# ext_board.net
KiCad netlist of a schematic drawn in EAGLE
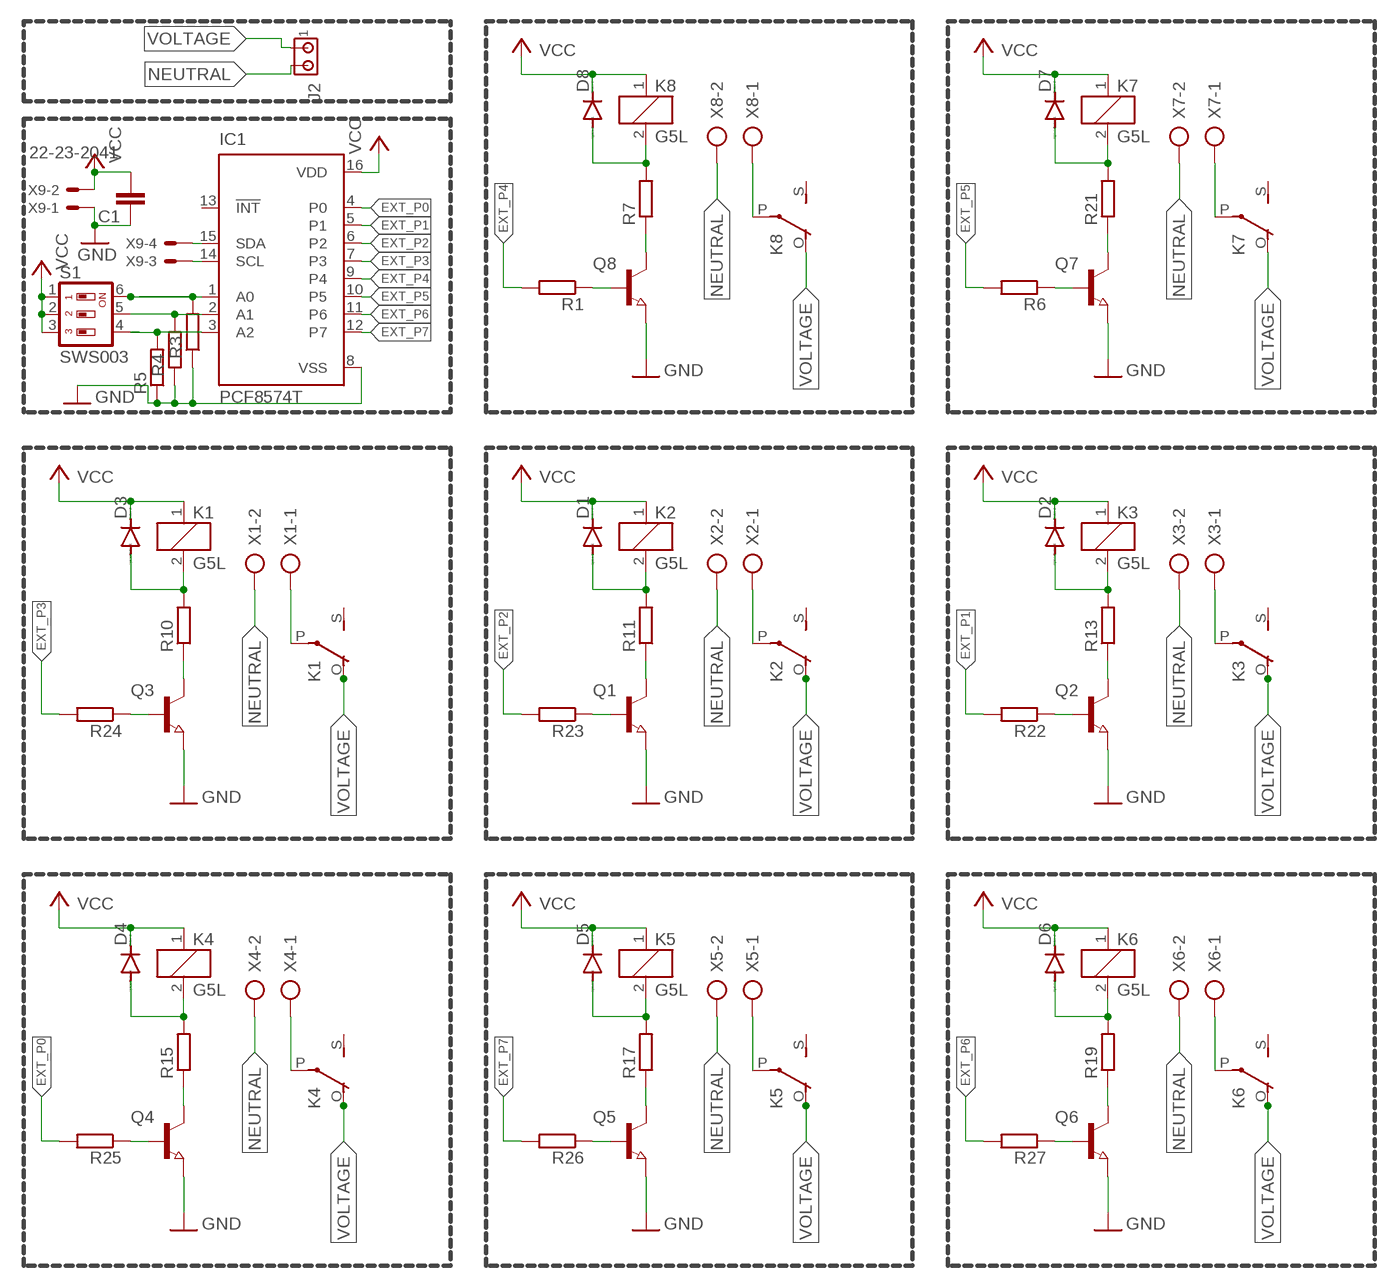
[diagram p0: schematic, sheet 1]

(export (version "E")
  (design (tool "Eeschema 10.0.6"))
  (components
    (comp (ref "C1")
      (value "C-EUC2012")
      (footprint "eagle-import:C2012")
      (libsource (lib "eagle-import") (part "C-EUC2012"))
    )
    (comp (ref "D1")
      (value "DIODE-DO-214AC")
      (footprint "eagle-import:DO-214AC")
      (libsource (lib "eagle-import") (part "DIODE-DO-214AC"))
    )
    (comp (ref "D2")
      (value "DIODE-DO-214AC")
      (footprint "eagle-import:DO-214AC")
      (libsource (lib "eagle-import") (part "DIODE-DO-214AC"))
    )
    (comp (ref "D3")
      (value "DIODE-DO-214AC")
      (footprint "eagle-import:DO-214AC")
      (libsource (lib "eagle-import") (part "DIODE-DO-214AC"))
    )
    (comp (ref "D4")
      (value "DIODE-DO-214AC")
      (footprint "eagle-import:DO-214AC")
      (libsource (lib "eagle-import") (part "DIODE-DO-214AC"))
    )
    (comp (ref "D5")
      (value "DIODE-DO-214AC")
      (footprint "eagle-import:DO-214AC")
      (libsource (lib "eagle-import") (part "DIODE-DO-214AC"))
    )
    (comp (ref "D6")
      (value "DIODE-DO-214AC")
      (footprint "eagle-import:DO-214AC")
      (libsource (lib "eagle-import") (part "DIODE-DO-214AC"))
    )
    (comp (ref "D7")
      (value "DIODE-DO-214AC")
      (footprint "eagle-import:DO-214AC")
      (libsource (lib "eagle-import") (part "DIODE-DO-214AC"))
    )
    (comp (ref "D8")
      (value "DIODE-DO-214AC")
      (footprint "eagle-import:DO-214AC")
      (libsource (lib "eagle-import") (part "DIODE-DO-214AC"))
    )
    (comp (ref "IC1")
      (value "PCF8574T")
      (footprint "eagle-import:SO16W")
      (fields (field (name "MPN") "PCF8574T/3,512"))
      (libsource (lib "eagle-import") (part "PCF8574T"))
    )
    (comp (ref "J2")
      (value "MTA02-156")
      (footprint "eagle-import:1X2MTA")
      (libsource (lib "eagle-import") (part "MTA02-156"))
    )
    (comp (ref "K1")
      (value "G5L")
      (footprint "eagle-import:G5LE")
      (libsource (lib "eagle-import") (part "G5L"))
    )
    (comp (ref "K2")
      (value "G5L")
      (footprint "eagle-import:G5LE")
      (libsource (lib "eagle-import") (part "G5L"))
    )
    (comp (ref "K3")
      (value "G5L")
      (footprint "eagle-import:G5LE")
      (libsource (lib "eagle-import") (part "G5L"))
    )
    (comp (ref "K4")
      (value "G5L")
      (footprint "eagle-import:G5LE")
      (libsource (lib "eagle-import") (part "G5L"))
    )
    (comp (ref "K5")
      (value "G5L")
      (footprint "eagle-import:G5LE")
      (libsource (lib "eagle-import") (part "G5L"))
    )
    (comp (ref "K6")
      (value "G5L")
      (footprint "eagle-import:G5LE")
      (libsource (lib "eagle-import") (part "G5L"))
    )
    (comp (ref "K7")
      (value "G5L")
      (footprint "eagle-import:G5LE")
      (libsource (lib "eagle-import") (part "G5L"))
    )
    (comp (ref "K8")
      (value "G5L")
      (footprint "eagle-import:G5LE")
      (libsource (lib "eagle-import") (part "G5L"))
    )
    (comp (ref "Q1")
      (value "NPN-TRANSISTOR_SOT23")
      (footprint "eagle-import:SOT23")
      (libsource (lib "eagle-import") (part "NPN-TRANSISTOR_SOT23"))
    )
    (comp (ref "Q2")
      (value "NPN-TRANSISTOR_SOT23")
      (footprint "eagle-import:SOT23")
      (libsource (lib "eagle-import") (part "NPN-TRANSISTOR_SOT23"))
    )
    (comp (ref "Q3")
      (value "NPN-TRANSISTOR_SOT23")
      (footprint "eagle-import:SOT23")
      (libsource (lib "eagle-import") (part "NPN-TRANSISTOR_SOT23"))
    )
    (comp (ref "Q4")
      (value "NPN-TRANSISTOR_SOT23")
      (footprint "eagle-import:SOT23")
      (libsource (lib "eagle-import") (part "NPN-TRANSISTOR_SOT23"))
    )
    (comp (ref "Q5")
      (value "NPN-TRANSISTOR_SOT23")
      (footprint "eagle-import:SOT23")
      (libsource (lib "eagle-import") (part "NPN-TRANSISTOR_SOT23"))
    )
    (comp (ref "Q6")
      (value "NPN-TRANSISTOR_SOT23")
      (footprint "eagle-import:SOT23")
      (libsource (lib "eagle-import") (part "NPN-TRANSISTOR_SOT23"))
    )
    (comp (ref "Q7")
      (value "NPN-TRANSISTOR_SOT23")
      (footprint "eagle-import:SOT23")
      (libsource (lib "eagle-import") (part "NPN-TRANSISTOR_SOT23"))
    )
    (comp (ref "Q8")
      (value "NPN-TRANSISTOR_SOT23")
      (footprint "eagle-import:SOT23")
      (libsource (lib "eagle-import") (part "NPN-TRANSISTOR_SOT23"))
    )
    (comp (ref "R1")
      (value "R-EU_R2010")
      (footprint "eagle-import:R2010")
      (libsource (lib "eagle-import") (part "R-EU_R2010"))
    )
    (comp (ref "R3")
      (value "R-EU_M2012")
      (footprint "eagle-import:M2012")
      (libsource (lib "eagle-import") (part "R-EU_M2012"))
    )
    (comp (ref "R4")
      (value "R-EU_M2012")
      (footprint "eagle-import:M2012")
      (libsource (lib "eagle-import") (part "R-EU_M2012"))
    )
    (comp (ref "R5")
      (value "R-EU_M2012")
      (footprint "eagle-import:M2012")
      (libsource (lib "eagle-import") (part "R-EU_M2012"))
    )
    (comp (ref "R6")
      (value "R-EU_R2010")
      (footprint "eagle-import:R2010")
      (libsource (lib "eagle-import") (part "R-EU_R2010"))
    )
    (comp (ref "R7")
      (value "R-EU_M2012")
      (footprint "eagle-import:M2012")
      (libsource (lib "eagle-import") (part "R-EU_M2012"))
    )
    (comp (ref "R10")
      (value "R-EU_M2012")
      (footprint "eagle-import:M2012")
      (libsource (lib "eagle-import") (part "R-EU_M2012"))
    )
    (comp (ref "R11")
      (value "R-EU_M2012")
      (footprint "eagle-import:M2012")
      (libsource (lib "eagle-import") (part "R-EU_M2012"))
    )
    (comp (ref "R13")
      (value "R-EU_M2012")
      (footprint "eagle-import:M2012")
      (libsource (lib "eagle-import") (part "R-EU_M2012"))
    )
    (comp (ref "R15")
      (value "R-EU_M2012")
      (footprint "eagle-import:M2012")
      (libsource (lib "eagle-import") (part "R-EU_M2012"))
    )
    (comp (ref "R17")
      (value "R-EU_M2012")
      (footprint "eagle-import:M2012")
      (libsource (lib "eagle-import") (part "R-EU_M2012"))
    )
    (comp (ref "R19")
      (value "R-EU_M2012")
      (footprint "eagle-import:M2012")
      (libsource (lib "eagle-import") (part "R-EU_M2012"))
    )
    (comp (ref "R21")
      (value "R-EU_M2012")
      (footprint "eagle-import:M2012")
      (libsource (lib "eagle-import") (part "R-EU_M2012"))
    )
    (comp (ref "R22")
      (value "R-EU_R2010")
      (footprint "eagle-import:R2010")
      (libsource (lib "eagle-import") (part "R-EU_R2010"))
    )
    (comp (ref "R23")
      (value "R-EU_R2010")
      (footprint "eagle-import:R2010")
      (libsource (lib "eagle-import") (part "R-EU_R2010"))
    )
    (comp (ref "R24")
      (value "R-EU_R2010")
      (footprint "eagle-import:R2010")
      (libsource (lib "eagle-import") (part "R-EU_R2010"))
    )
    (comp (ref "R25")
      (value "R-EU_R2010")
      (footprint "eagle-import:R2010")
      (libsource (lib "eagle-import") (part "R-EU_R2010"))
    )
    (comp (ref "R26")
      (value "R-EU_R2010")
      (footprint "eagle-import:R2010")
      (libsource (lib "eagle-import") (part "R-EU_R2010"))
    )
    (comp (ref "R27")
      (value "R-EU_R2010")
      (footprint "eagle-import:R2010")
      (libsource (lib "eagle-import") (part "R-EU_R2010"))
    )
    (comp (ref "S1")
      (value "SWS003")
      (footprint "eagle-import:SMS-003")
      (libsource (lib "eagle-import") (part "SWS003"))
    )
    (comp (ref "X1")
      (value "AK300/2")
      (footprint "eagle-import:AK300_2")
      (libsource (lib "eagle-import") (part "AK300/2"))
    )
    (comp (ref "X2")
      (value "AK300/2")
      (footprint "eagle-import:AK300_2")
      (libsource (lib "eagle-import") (part "AK300/2"))
    )
    (comp (ref "X3")
      (value "AK300/2")
      (footprint "eagle-import:AK300_2")
      (libsource (lib "eagle-import") (part "AK300/2"))
    )
    (comp (ref "X4")
      (value "AK300/2")
      (footprint "eagle-import:AK300_2")
      (libsource (lib "eagle-import") (part "AK300/2"))
    )
    (comp (ref "X5")
      (value "AK300/2")
      (footprint "eagle-import:AK300_2")
      (libsource (lib "eagle-import") (part "AK300/2"))
    )
    (comp (ref "X6")
      (value "AK300/2")
      (footprint "eagle-import:AK300_2")
      (libsource (lib "eagle-import") (part "AK300/2"))
    )
    (comp (ref "X7")
      (value "AK300/2")
      (footprint "eagle-import:AK300_2")
      (libsource (lib "eagle-import") (part "AK300/2"))
    )
    (comp (ref "X8")
      (value "AK300/2")
      (footprint "eagle-import:AK300_2")
      (libsource (lib "eagle-import") (part "AK300/2"))
    )
    (comp (ref "X9")
      (value "22-23-2041")
      (footprint "eagle-import:22-23-2041")
      (fields (field (name "MF") "MOLEX"))
      (libsource (lib "eagle-import") (part "22-23-2041"))
    )
  )
  (nets
    (net (code "1") (name "EXT_P0") (class "Default")
      (node (ref "IC1") (pin "4") (pinfunction "P0_4") (pintype "bidirectional"))
      (node (ref "R25") (pin "2") (pinfunction "2_2") (pintype "passive"))
    )
    (net (code "2") (name "EXT_P1") (class "Default")
      (node (ref "IC1") (pin "5") (pinfunction "P1_5") (pintype "bidirectional"))
      (node (ref "R22") (pin "2") (pinfunction "2_2") (pintype "passive"))
    )
    (net (code "3") (name "EXT_P2") (class "Default")
      (node (ref "IC1") (pin "6") (pinfunction "P2_6") (pintype "bidirectional"))
      (node (ref "R23") (pin "2") (pinfunction "2_2") (pintype "passive"))
    )
    (net (code "4") (name "EXT_P3") (class "Default")
      (node (ref "IC1") (pin "7") (pinfunction "P3_7") (pintype "bidirectional"))
      (node (ref "R24") (pin "2") (pinfunction "2_2") (pintype "passive"))
    )
    (net (code "5") (name "EXT_P4") (class "Default")
      (node (ref "IC1") (pin "9") (pinfunction "P4_9") (pintype "bidirectional"))
      (node (ref "R1") (pin "2") (pinfunction "2_2") (pintype "passive"))
    )
    (net (code "6") (name "EXT_P5") (class "Default")
      (node (ref "IC1") (pin "10") (pinfunction "P5_10") (pintype "bidirectional"))
      (node (ref "R6") (pin "2") (pinfunction "2_2") (pintype "passive"))
    )
    (net (code "7") (name "EXT_P6") (class "Default")
      (node (ref "IC1") (pin "11") (pinfunction "P6_11") (pintype "bidirectional"))
      (node (ref "R27") (pin "2") (pinfunction "2_2") (pintype "passive"))
    )
    (net (code "8") (name "EXT_P7") (class "Default")
      (node (ref "IC1") (pin "12") (pinfunction "P7_12") (pintype "bidirectional"))
      (node (ref "R26") (pin "2") (pinfunction "2_2") (pintype "passive"))
    )
    (net (code "9") (name "GND") (class "Default")
      (node (ref "C1") (pin "1") (pinfunction "1_1") (pintype "passive"))
      (node (ref "IC1") (pin "8") (pinfunction "VSS_8") (pintype "power_in"))
      (node (ref "Q1") (pin "2") (pinfunction "E_2") (pintype "passive"))
      (node (ref "Q2") (pin "2") (pinfunction "E_2") (pintype "passive"))
      (node (ref "Q3") (pin "2") (pinfunction "E_2") (pintype "passive"))
      (node (ref "Q4") (pin "2") (pinfunction "E_2") (pintype "passive"))
      (node (ref "Q5") (pin "2") (pinfunction "E_2") (pintype "passive"))
      (node (ref "Q6") (pin "2") (pinfunction "E_2") (pintype "passive"))
      (node (ref "Q7") (pin "2") (pinfunction "E_2") (pintype "passive"))
      (node (ref "Q8") (pin "2") (pinfunction "E_2") (pintype "passive"))
      (node (ref "R3") (pin "1") (pinfunction "1_1") (pintype "passive"))
      (node (ref "R4") (pin "1") (pinfunction "1_1") (pintype "passive"))
      (node (ref "R5") (pin "1") (pinfunction "1_1") (pintype "passive"))
      (node (ref "X9") (pin "1") (pinfunction "S_1") (pintype "passive"))
    )
    (net (code "10") (name "NEUTRAL") (class "Default")
      (node (ref "J2") (pin "2") (pinfunction "2_2") (pintype "passive"))
      (node (ref "X1") (pin "2") (pinfunction "KL_2") (pintype "passive"))
      (node (ref "X2") (pin "2") (pinfunction "KL_2") (pintype "passive"))
      (node (ref "X3") (pin "2") (pinfunction "KL_2") (pintype "passive"))
      (node (ref "X4") (pin "2") (pinfunction "KL_2") (pintype "passive"))
      (node (ref "X5") (pin "2") (pinfunction "KL_2") (pintype "passive"))
      (node (ref "X6") (pin "2") (pinfunction "KL_2") (pintype "passive"))
      (node (ref "X7") (pin "2") (pinfunction "KL_2") (pintype "passive"))
      (node (ref "X8") (pin "2") (pinfunction "KL_2") (pintype "passive"))
    )
    (net (code "11") (name "Net-(D1-PadA)") (class "Default")
      (node (ref "D1") (pin "A") (pinfunction "A_A") (pintype "passive"))
      (node (ref "K2") (pin "2") (pinfunction "2_2") (pintype "passive"))
      (node (ref "R11") (pin "2") (pinfunction "2_2") (pintype "passive"))
    )
    (net (code "12") (name "Net-(D2-PadA)") (class "Default")
      (node (ref "D2") (pin "A") (pinfunction "A_A") (pintype "passive"))
      (node (ref "K3") (pin "2") (pinfunction "2_2") (pintype "passive"))
      (node (ref "R13") (pin "2") (pinfunction "2_2") (pintype "passive"))
    )
    (net (code "13") (name "Net-(D3-PadA)") (class "Default")
      (node (ref "D3") (pin "A") (pinfunction "A_A") (pintype "passive"))
      (node (ref "K1") (pin "2") (pinfunction "2_2") (pintype "passive"))
      (node (ref "R10") (pin "2") (pinfunction "2_2") (pintype "passive"))
    )
    (net (code "14") (name "Net-(D4-PadA)") (class "Default")
      (node (ref "D4") (pin "A") (pinfunction "A_A") (pintype "passive"))
      (node (ref "K4") (pin "2") (pinfunction "2_2") (pintype "passive"))
      (node (ref "R15") (pin "2") (pinfunction "2_2") (pintype "passive"))
    )
    (net (code "15") (name "Net-(D5-PadA)") (class "Default")
      (node (ref "D5") (pin "A") (pinfunction "A_A") (pintype "passive"))
      (node (ref "K5") (pin "2") (pinfunction "2_2") (pintype "passive"))
      (node (ref "R17") (pin "2") (pinfunction "2_2") (pintype "passive"))
    )
    (net (code "16") (name "Net-(D6-PadA)") (class "Default")
      (node (ref "D6") (pin "A") (pinfunction "A_A") (pintype "passive"))
      (node (ref "K6") (pin "2") (pinfunction "2_2") (pintype "passive"))
      (node (ref "R19") (pin "2") (pinfunction "2_2") (pintype "passive"))
    )
    (net (code "17") (name "Net-(D7-PadA)") (class "Default")
      (node (ref "D7") (pin "A") (pinfunction "A_A") (pintype "passive"))
      (node (ref "K7") (pin "2") (pinfunction "2_2") (pintype "passive"))
      (node (ref "R21") (pin "2") (pinfunction "2_2") (pintype "passive"))
    )
    (net (code "18") (name "Net-(D8-PadA)") (class "Default")
      (node (ref "D8") (pin "A") (pinfunction "A_A") (pintype "passive"))
      (node (ref "K8") (pin "2") (pinfunction "2_2") (pintype "passive"))
      (node (ref "R7") (pin "2") (pinfunction "2_2") (pintype "passive"))
    )
    (net (code "19") (name "Net-(IC1-A0)") (class "Default")
      (node (ref "IC1") (pin "1") (pinfunction "A0_1") (pintype "input"))
      (node (ref "R3") (pin "2") (pinfunction "2_2") (pintype "passive"))
      (node (ref "S1") (pin "6") (pinfunction "6_6") (pintype "passive"))
    )
    (net (code "20") (name "Net-(IC1-A1)") (class "Default")
      (node (ref "IC1") (pin "2") (pinfunction "A1_2") (pintype "input"))
      (node (ref "R4") (pin "2") (pinfunction "2_2") (pintype "passive"))
      (node (ref "S1") (pin "5") (pinfunction "5_5") (pintype "passive"))
    )
    (net (code "21") (name "Net-(IC1-A2)") (class "Default")
      (node (ref "IC1") (pin "3") (pinfunction "A2_3") (pintype "input"))
      (node (ref "R5") (pin "2") (pinfunction "2_2") (pintype "passive"))
      (node (ref "S1") (pin "4") (pinfunction "4_4") (pintype "passive"))
    )
    (net (code "22") (name "Net-(IC1-SCL)") (class "Default")
      (node (ref "IC1") (pin "14") (pinfunction "SCL_14") (pintype "input"))
      (node (ref "X9") (pin "3") (pinfunction "S_3") (pintype "passive"))
    )
    (net (code "23") (name "Net-(IC1-SDA)") (class "Default")
      (node (ref "IC1") (pin "15") (pinfunction "SDA_15") (pintype "bidirectional"))
      (node (ref "X9") (pin "4") (pinfunction "S_4") (pintype "passive"))
    )
    (net (code "24") (name "Net-(Q1-B)") (class "Default")
      (node (ref "Q1") (pin "1") (pinfunction "B_1") (pintype "passive"))
      (node (ref "R23") (pin "1") (pinfunction "1_1") (pintype "passive"))
    )
    (net (code "25") (name "Net-(Q1-C)") (class "Default")
      (node (ref "Q1") (pin "3") (pinfunction "C_3") (pintype "passive"))
      (node (ref "R11") (pin "1") (pinfunction "1_1") (pintype "passive"))
    )
    (net (code "26") (name "Net-(Q2-B)") (class "Default")
      (node (ref "Q2") (pin "1") (pinfunction "B_1") (pintype "passive"))
      (node (ref "R22") (pin "1") (pinfunction "1_1") (pintype "passive"))
    )
    (net (code "27") (name "Net-(Q2-C)") (class "Default")
      (node (ref "Q2") (pin "3") (pinfunction "C_3") (pintype "passive"))
      (node (ref "R13") (pin "1") (pinfunction "1_1") (pintype "passive"))
    )
    (net (code "28") (name "Net-(Q3-B)") (class "Default")
      (node (ref "Q3") (pin "1") (pinfunction "B_1") (pintype "passive"))
      (node (ref "R24") (pin "1") (pinfunction "1_1") (pintype "passive"))
    )
    (net (code "29") (name "Net-(Q3-C)") (class "Default")
      (node (ref "Q3") (pin "3") (pinfunction "C_3") (pintype "passive"))
      (node (ref "R10") (pin "1") (pinfunction "1_1") (pintype "passive"))
    )
    (net (code "30") (name "Net-(Q4-B)") (class "Default")
      (node (ref "Q4") (pin "1") (pinfunction "B_1") (pintype "passive"))
      (node (ref "R25") (pin "1") (pinfunction "1_1") (pintype "passive"))
    )
    (net (code "31") (name "Net-(Q4-C)") (class "Default")
      (node (ref "Q4") (pin "3") (pinfunction "C_3") (pintype "passive"))
      (node (ref "R15") (pin "1") (pinfunction "1_1") (pintype "passive"))
    )
    (net (code "32") (name "Net-(Q5-B)") (class "Default")
      (node (ref "Q5") (pin "1") (pinfunction "B_1") (pintype "passive"))
      (node (ref "R26") (pin "1") (pinfunction "1_1") (pintype "passive"))
    )
    (net (code "33") (name "Net-(Q5-C)") (class "Default")
      (node (ref "Q5") (pin "3") (pinfunction "C_3") (pintype "passive"))
      (node (ref "R17") (pin "1") (pinfunction "1_1") (pintype "passive"))
    )
    (net (code "34") (name "Net-(Q6-B)") (class "Default")
      (node (ref "Q6") (pin "1") (pinfunction "B_1") (pintype "passive"))
      (node (ref "R27") (pin "1") (pinfunction "1_1") (pintype "passive"))
    )
    (net (code "35") (name "Net-(Q6-C)") (class "Default")
      (node (ref "Q6") (pin "3") (pinfunction "C_3") (pintype "passive"))
      (node (ref "R19") (pin "1") (pinfunction "1_1") (pintype "passive"))
    )
    (net (code "36") (name "Net-(Q7-B)") (class "Default")
      (node (ref "Q7") (pin "1") (pinfunction "B_1") (pintype "passive"))
      (node (ref "R6") (pin "1") (pinfunction "1_1") (pintype "passive"))
    )
    (net (code "37") (name "Net-(Q7-C)") (class "Default")
      (node (ref "Q7") (pin "3") (pinfunction "C_3") (pintype "passive"))
      (node (ref "R21") (pin "1") (pinfunction "1_1") (pintype "passive"))
    )
    (net (code "38") (name "Net-(Q8-B)") (class "Default")
      (node (ref "Q8") (pin "1") (pinfunction "B_1") (pintype "passive"))
      (node (ref "R1") (pin "1") (pinfunction "1_1") (pintype "passive"))
    )
    (net (code "39") (name "Net-(Q8-C)") (class "Default")
      (node (ref "Q8") (pin "3") (pinfunction "C_3") (pintype "passive"))
      (node (ref "R7") (pin "1") (pinfunction "1_1") (pintype "passive"))
    )
    (net (code "40") (name "Net-(X1A-KL)") (class "Default")
      (node (ref "K1") (pin "P") (pinfunction "P_P") (pintype "passive"))
      (node (ref "X1") (pin "1") (pinfunction "KL_1") (pintype "passive"))
    )
    (net (code "41") (name "Net-(X2A-KL)") (class "Default")
      (node (ref "K2") (pin "P") (pinfunction "P_P") (pintype "passive"))
      (node (ref "X2") (pin "1") (pinfunction "KL_1") (pintype "passive"))
    )
    (net (code "42") (name "Net-(X3A-KL)") (class "Default")
      (node (ref "K3") (pin "P") (pinfunction "P_P") (pintype "passive"))
      (node (ref "X3") (pin "1") (pinfunction "KL_1") (pintype "passive"))
    )
    (net (code "43") (name "Net-(X4A-KL)") (class "Default")
      (node (ref "K4") (pin "P") (pinfunction "P_P") (pintype "passive"))
      (node (ref "X4") (pin "1") (pinfunction "KL_1") (pintype "passive"))
    )
    (net (code "44") (name "Net-(X5A-KL)") (class "Default")
      (node (ref "K5") (pin "P") (pinfunction "P_P") (pintype "passive"))
      (node (ref "X5") (pin "1") (pinfunction "KL_1") (pintype "passive"))
    )
    (net (code "45") (name "Net-(X6A-KL)") (class "Default")
      (node (ref "K6") (pin "P") (pinfunction "P_P") (pintype "passive"))
      (node (ref "X6") (pin "1") (pinfunction "KL_1") (pintype "passive"))
    )
    (net (code "46") (name "Net-(X7A-KL)") (class "Default")
      (node (ref "K7") (pin "P") (pinfunction "P_P") (pintype "passive"))
      (node (ref "X7") (pin "1") (pinfunction "KL_1") (pintype "passive"))
    )
    (net (code "47") (name "Net-(X8A-KL)") (class "Default")
      (node (ref "K8") (pin "P") (pinfunction "P_P") (pintype "passive"))
      (node (ref "X8") (pin "1") (pinfunction "KL_1") (pintype "passive"))
    )
    (net (code "48") (name "VCC") (class "Default")
      (node (ref "C1") (pin "2") (pinfunction "2_2") (pintype "passive"))
      (node (ref "D1") (pin "C") (pinfunction "C_C") (pintype "passive"))
      (node (ref "D2") (pin "C") (pinfunction "C_C") (pintype "passive"))
      (node (ref "D3") (pin "C") (pinfunction "C_C") (pintype "passive"))
      (node (ref "D4") (pin "C") (pinfunction "C_C") (pintype "passive"))
      (node (ref "D5") (pin "C") (pinfunction "C_C") (pintype "passive"))
      (node (ref "D6") (pin "C") (pinfunction "C_C") (pintype "passive"))
      (node (ref "D7") (pin "C") (pinfunction "C_C") (pintype "passive"))
      (node (ref "D8") (pin "C") (pinfunction "C_C") (pintype "passive"))
      (node (ref "IC1") (pin "16") (pinfunction "VDD_16") (pintype "power_in"))
      (node (ref "K1") (pin "1") (pinfunction "1_1") (pintype "passive"))
      (node (ref "K2") (pin "1") (pinfunction "1_1") (pintype "passive"))
      (node (ref "K3") (pin "1") (pinfunction "1_1") (pintype "passive"))
      (node (ref "K4") (pin "1") (pinfunction "1_1") (pintype "passive"))
      (node (ref "K5") (pin "1") (pinfunction "1_1") (pintype "passive"))
      (node (ref "K6") (pin "1") (pinfunction "1_1") (pintype "passive"))
      (node (ref "K7") (pin "1") (pinfunction "1_1") (pintype "passive"))
      (node (ref "K8") (pin "1") (pinfunction "1_1") (pintype "passive"))
      (node (ref "S1") (pin "1") (pinfunction "1_1") (pintype "passive"))
      (node (ref "S1") (pin "2") (pinfunction "2_2") (pintype "passive"))
      (node (ref "S1") (pin "3") (pinfunction "3_3") (pintype "passive"))
      (node (ref "X9") (pin "2") (pinfunction "S_2") (pintype "passive"))
    )
    (net (code "49") (name "VOLTAGE") (class "Default")
      (node (ref "J2") (pin "1") (pinfunction "1_1") (pintype "passive"))
      (node (ref "K1") (pin "O") (pinfunction "O_O") (pintype "passive"))
      (node (ref "K2") (pin "O") (pinfunction "O_O") (pintype "passive"))
      (node (ref "K3") (pin "O") (pinfunction "O_O") (pintype "passive"))
      (node (ref "K4") (pin "O") (pinfunction "O_O") (pintype "passive"))
      (node (ref "K5") (pin "O") (pinfunction "O_O") (pintype "passive"))
      (node (ref "K6") (pin "O") (pinfunction "O_O") (pintype "passive"))
      (node (ref "K7") (pin "O") (pinfunction "O_O") (pintype "passive"))
      (node (ref "K8") (pin "O") (pinfunction "O_O") (pintype "passive"))
    )
    (net (code "50") (name "unconnected-(IC1-~{INT}-Pad13)") (class "Default")
      (node (ref "IC1") (pin "13") (pinfunction "~{INT}_13") (pintype "output"))
    )
    (net (code "51") (name "unconnected-(K1-PadS)") (class "Default")
      (node (ref "K1") (pin "S") (pinfunction "S_S") (pintype "passive"))
    )
    (net (code "52") (name "unconnected-(K2-PadS)") (class "Default")
      (node (ref "K2") (pin "S") (pinfunction "S_S") (pintype "passive"))
    )
    (net (code "53") (name "unconnected-(K3-PadS)") (class "Default")
      (node (ref "K3") (pin "S") (pinfunction "S_S") (pintype "passive"))
    )
    (net (code "54") (name "unconnected-(K4-PadS)") (class "Default")
      (node (ref "K4") (pin "S") (pinfunction "S_S") (pintype "passive"))
    )
    (net (code "55") (name "unconnected-(K5-PadS)") (class "Default")
      (node (ref "K5") (pin "S") (pinfunction "S_S") (pintype "passive"))
    )
    (net (code "56") (name "unconnected-(K6-PadS)") (class "Default")
      (node (ref "K6") (pin "S") (pinfunction "S_S") (pintype "passive"))
    )
    (net (code "57") (name "unconnected-(K7-PadS)") (class "Default")
      (node (ref "K7") (pin "S") (pinfunction "S_S") (pintype "passive"))
    )
    (net (code "58") (name "unconnected-(K8-PadS)") (class "Default")
      (node (ref "K8") (pin "S") (pinfunction "S_S") (pintype "passive"))
    )
  )
)
